# POWER_METER.net
KiCad netlist of a schematic drawn in EAGLE
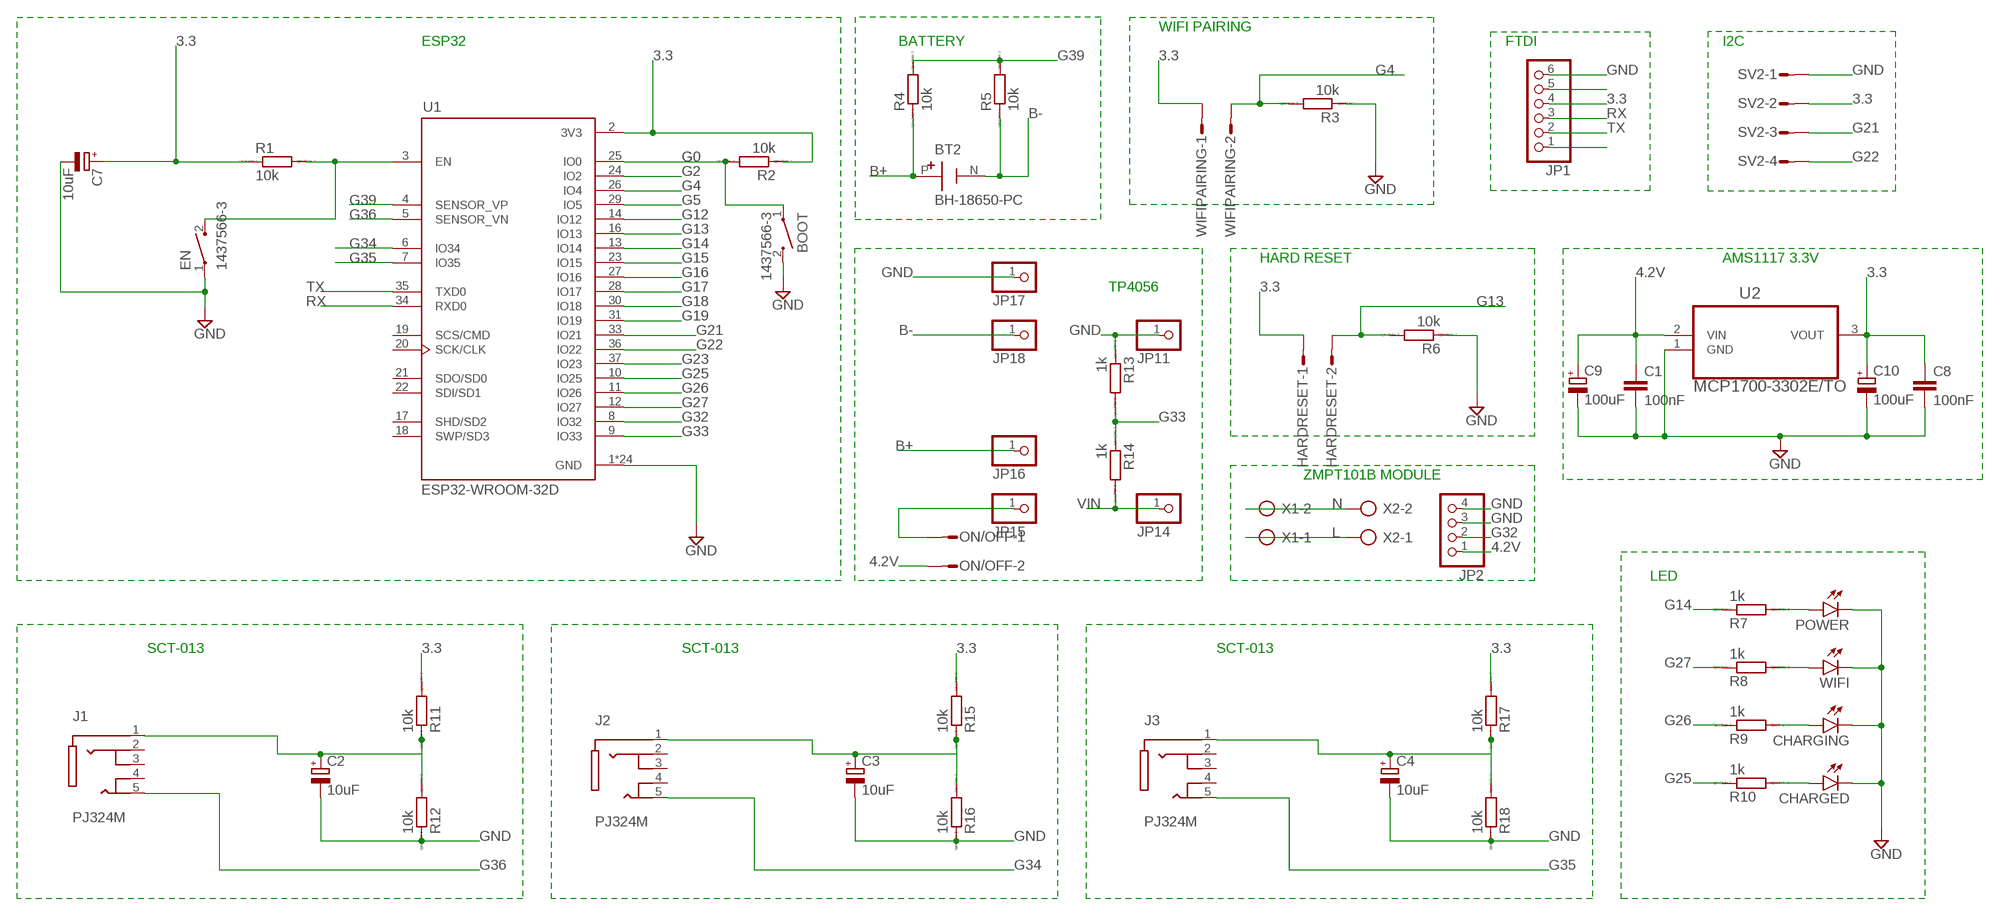
[diagram p0: schematic, sheet 1]

(export (version "E")
  (design (tool "Eeschema 10.0.6"))
  (components
    (comp (ref "BOOT")
      (value "1437566-3")
      (footprint "eagle-import:SW_1437566-3")
      (fields (field (name "MF") "TE Connectivity"))
      (libsource (lib "eagle-import") (part "1437566-3"))
    )
    (comp (ref "BT2")
      (value "BH-18650-PC")
      (footprint "eagle-import:BAT_BH-18650-PC")
      (fields (field (name "MF") "MPD (Memory"))
      (libsource (lib "eagle-import") (part "BH-18650-PC"))
    )
    (comp (ref "C1")
      (value "100nF")
      (footprint "eagle-import:C1206K")
      (libsource (lib "eagle-import") (part "C-EUC1206K"))
    )
    (comp (ref "C2")
      (value "10uF")
      (footprint "eagle-import:E2,5-6")
      (libsource (lib "eagle-import") (part "CPOL-EUE2.5-6"))
    )
    (comp (ref "C3")
      (value "10uF")
      (footprint "eagle-import:E2,5-6")
      (libsource (lib "eagle-import") (part "CPOL-EUE2.5-6"))
    )
    (comp (ref "C4")
      (value "10uF")
      (footprint "eagle-import:E2,5-6")
      (libsource (lib "eagle-import") (part "CPOL-EUE2.5-6"))
    )
    (comp (ref "C7")
      (value "10uF")
      (footprint "eagle-import:E2,5-6")
      (libsource (lib "eagle-import") (part "CPOL-EUE2.5-6"))
    )
    (comp (ref "C8")
      (value "100nF")
      (footprint "eagle-import:C1206K")
      (libsource (lib "eagle-import") (part "C-EUC1206K"))
    )
    (comp (ref "C9")
      (value "100uF")
      (footprint "eagle-import:E2,5-6")
      (libsource (lib "eagle-import") (part "CPOL-EUE2.5-6"))
    )
    (comp (ref "C10")
      (value "100uF")
      (footprint "eagle-import:E2,5-6")
      (libsource (lib "eagle-import") (part "CPOL-EUE2.5-6"))
    )
    (comp (ref "CHARGED")
      (value "LEDCHIPLED_1206")
      (footprint "eagle-import:CHIPLED_1206")
      (libsource (lib "eagle-import") (part "LEDCHIPLED_1206"))
    )
    (comp (ref "CHARGING")
      (value "LEDCHIPLED_1206")
      (footprint "eagle-import:CHIPLED_1206")
      (libsource (lib "eagle-import") (part "LEDCHIPLED_1206"))
    )
    (comp (ref "EN")
      (value "1437566-3")
      (footprint "eagle-import:SW_1437566-3")
      (fields (field (name "MF") "TE Connectivity"))
      (libsource (lib "eagle-import") (part "1437566-3"))
    )
    (comp (ref "HARDRESET")
      (value "S02P")
      (footprint "eagle-import:S02P")
      (libsource (lib "eagle-import") (part "S02P"))
    )
    (comp (ref "J1")
      (value "PJ324M")
      (footprint "eagle-import:WENZHOU_PJ324M")
      (fields (field (name "MF") "Wenzhou QingPu Electronics Co.Ltd"))
      (libsource (lib "eagle-import") (part "PJ324M"))
    )
    (comp (ref "J2")
      (value "PJ324M")
      (footprint "eagle-import:WENZHOU_PJ324M")
      (fields (field (name "MF") "Wenzhou QingPu Electronics Co.Ltd"))
      (libsource (lib "eagle-import") (part "PJ324M"))
    )
    (comp (ref "J3")
      (value "PJ324M")
      (footprint "eagle-import:WENZHOU_PJ324M")
      (fields (field (name "MF") "Wenzhou QingPu Electronics Co.Ltd"))
      (libsource (lib "eagle-import") (part "PJ324M"))
    )
    (comp (ref "JP1")
      (value "PINHD-1X6/90")
      (footprint "eagle-import:1X06_90")
      (libsource (lib "eagle-import") (part "PINHD-1X6/90"))
    )
    (comp (ref "JP2")
      (value "PINHD-1X4")
      (footprint "eagle-import:1X04")
      (libsource (lib "eagle-import") (part "PINHD-1X4"))
    )
    (comp (ref "JP11")
      (value "PINHD-1X1")
      (footprint "eagle-import:1X01")
      (libsource (lib "eagle-import") (part "PINHD-1X1"))
    )
    (comp (ref "JP14")
      (value "PINHD-1X1")
      (footprint "eagle-import:1X01")
      (libsource (lib "eagle-import") (part "PINHD-1X1"))
    )
    (comp (ref "JP15")
      (value "PINHD-1X1")
      (footprint "eagle-import:1X01")
      (libsource (lib "eagle-import") (part "PINHD-1X1"))
    )
    (comp (ref "JP16")
      (value "PINHD-1X1")
      (footprint "eagle-import:1X01")
      (libsource (lib "eagle-import") (part "PINHD-1X1"))
    )
    (comp (ref "JP17")
      (value "PINHD-1X1")
      (footprint "eagle-import:1X01")
      (libsource (lib "eagle-import") (part "PINHD-1X1"))
    )
    (comp (ref "JP18")
      (value "PINHD-1X1")
      (footprint "eagle-import:1X01")
      (libsource (lib "eagle-import") (part "PINHD-1X1"))
    )
    (comp (ref "ON/OFF")
      (value "S02P")
      (footprint "eagle-import:S02P")
      (libsource (lib "eagle-import") (part "S02P"))
    )
    (comp (ref "POWER")
      (value "LEDCHIPLED_1206")
      (footprint "eagle-import:CHIPLED_1206")
      (libsource (lib "eagle-import") (part "LEDCHIPLED_1206"))
    )
    (comp (ref "R1")
      (value "10k")
      (footprint "eagle-import:R1206")
      (libsource (lib "eagle-import") (part "RR1206"))
    )
    (comp (ref "R2")
      (value "10k")
      (footprint "eagle-import:R1206")
      (libsource (lib "eagle-import") (part "RR1206"))
    )
    (comp (ref "R3")
      (value "10k")
      (footprint "eagle-import:R1206")
      (libsource (lib "eagle-import") (part "RR1206"))
    )
    (comp (ref "R4")
      (value "10k")
      (footprint "eagle-import:R1206")
      (libsource (lib "eagle-import") (part "RR1206"))
    )
    (comp (ref "R5")
      (value "10k")
      (footprint "eagle-import:R1206")
      (libsource (lib "eagle-import") (part "RR1206"))
    )
    (comp (ref "R6")
      (value "10k")
      (footprint "eagle-import:R1206")
      (libsource (lib "eagle-import") (part "RR1206"))
    )
    (comp (ref "R7")
      (value "1k")
      (footprint "eagle-import:R1206")
      (libsource (lib "eagle-import") (part "RR1206"))
    )
    (comp (ref "R8")
      (value "1k")
      (footprint "eagle-import:R1206")
      (libsource (lib "eagle-import") (part "RR1206"))
    )
    (comp (ref "R9")
      (value "1k")
      (footprint "eagle-import:R1206")
      (libsource (lib "eagle-import") (part "RR1206"))
    )
    (comp (ref "R10")
      (value "1k")
      (footprint "eagle-import:R1206")
      (libsource (lib "eagle-import") (part "RR1206"))
    )
    (comp (ref "R11")
      (value "10k")
      (footprint "eagle-import:R1206")
      (libsource (lib "eagle-import") (part "RR1206"))
    )
    (comp (ref "R12")
      (value "10k")
      (footprint "eagle-import:R1206")
      (libsource (lib "eagle-import") (part "RR1206"))
    )
    (comp (ref "R13")
      (value "1k")
      (footprint "eagle-import:R1206")
      (libsource (lib "eagle-import") (part "RR1206"))
    )
    (comp (ref "R14")
      (value "1k")
      (footprint "eagle-import:R1206")
      (libsource (lib "eagle-import") (part "RR1206"))
    )
    (comp (ref "R15")
      (value "10k")
      (footprint "eagle-import:R1206")
      (libsource (lib "eagle-import") (part "RR1206"))
    )
    (comp (ref "R16")
      (value "10k")
      (footprint "eagle-import:R1206")
      (libsource (lib "eagle-import") (part "RR1206"))
    )
    (comp (ref "R17")
      (value "10k")
      (footprint "eagle-import:R1206")
      (libsource (lib "eagle-import") (part "RR1206"))
    )
    (comp (ref "R18")
      (value "10k")
      (footprint "eagle-import:R1206")
      (libsource (lib "eagle-import") (part "RR1206"))
    )
    (comp (ref "SV2")
      (value "S04P")
      (footprint "eagle-import:S04P")
      (libsource (lib "eagle-import") (part "S04P"))
    )
    (comp (ref "U1")
      (value "ESP32-WROOM-32D")
      (footprint "eagle-import:MODULE_ESP32-WROOM-32D")
      (fields (field (name "MF") "Espressif Systems"))
      (libsource (lib "eagle-import") (part "ESP32-WROOM-32D"))
    )
    (comp (ref "U2")
      (value "MCP1700-3302E/TO")
      (footprint "eagle-import:TO127P254X495-3")
      (fields (field (name "MF") "Microchip"))
      (libsource (lib "eagle-import") (part "MCP1700-3302E/TO"))
    )
    (comp (ref "WIFI")
      (value "LEDCHIPLED_1206")
      (footprint "eagle-import:CHIPLED_1206")
      (libsource (lib "eagle-import") (part "LEDCHIPLED_1206"))
    )
    (comp (ref "WIFIPAIRING")
      (value "S02P")
      (footprint "eagle-import:S02P")
      (libsource (lib "eagle-import") (part "S02P"))
    )
    (comp (ref "X1")
      (value "AK500/2")
      (footprint "eagle-import:AK500_2")
      (libsource (lib "eagle-import") (part "AK500/2"))
    )
    (comp (ref "X2")
      (value "AK500/2")
      (footprint "eagle-import:AK500_2")
      (libsource (lib "eagle-import") (part "AK500/2"))
    )
  )
  (nets
    (net (code "1") (name "/3.3") (class "Default")
      (node (ref "C10") (pin "+") (pinfunction "+_+") (pintype "passive"))
      (node (ref "C7") (pin "+") (pinfunction "+_+") (pintype "passive"))
      (node (ref "C8") (pin "1") (pinfunction "1_1") (pintype "passive"))
      (node (ref "HARDRESET") (pin "1") (pinfunction "S_1") (pintype "passive"))
      (node (ref "JP1") (pin "4") (pinfunction "4_4") (pintype "passive"))
      (node (ref "R1") (pin "1") (pinfunction "1_1") (pintype "passive"))
      (node (ref "R11") (pin "2") (pinfunction "2_2") (pintype "passive"))
      (node (ref "R15") (pin "2") (pinfunction "2_2") (pintype "passive"))
      (node (ref "R17") (pin "2") (pinfunction "2_2") (pintype "passive"))
      (node (ref "R2") (pin "1") (pinfunction "1_1") (pintype "passive"))
      (node (ref "SV2") (pin "2") (pinfunction "S_2") (pintype "passive"))
      (node (ref "U1") (pin "2") (pinfunction "3V3_2") (pintype "power_in"))
      (node (ref "U2") (pin "3") (pinfunction "VOUT_3") (pintype "output"))
      (node (ref "WIFIPAIRING") (pin "1") (pinfunction "S_1") (pintype "passive"))
    )
    (net (code "2") (name "/4.2V") (class "Default")
      (node (ref "C1") (pin "1") (pinfunction "1_1") (pintype "passive"))
      (node (ref "C9") (pin "+") (pinfunction "+_+") (pintype "passive"))
      (node (ref "JP2") (pin "1") (pinfunction "1_1") (pintype "passive"))
      (node (ref "ON/OFF") (pin "2") (pinfunction "S_2") (pintype "passive"))
      (node (ref "U2") (pin "2") (pinfunction "VIN_2") (pintype "input"))
    )
    (net (code "3") (name "/B+") (class "Default")
      (node (ref "BT2") (pin "P") (pinfunction "+_P") (pintype "passive"))
      (node (ref "JP16") (pin "1") (pinfunction "1_1") (pintype "passive"))
      (node (ref "R4") (pin "1") (pinfunction "1_1") (pintype "passive"))
    )
    (net (code "4") (name "/B-") (class "Default")
      (node (ref "BT2") (pin "N") (pinfunction "-_N") (pintype "passive"))
      (node (ref "JP18") (pin "1") (pinfunction "1_1") (pintype "passive"))
      (node (ref "R5") (pin "1") (pinfunction "1_1") (pintype "passive"))
    )
    (net (code "5") (name "/G0") (class "Default")
      (node (ref "BOOT") (pin "1") (pinfunction "1_1") (pintype "passive"))
      (node (ref "R2") (pin "2") (pinfunction "2_2") (pintype "passive"))
      (node (ref "U1") (pin "25") (pinfunction "IO0_25") (pintype "bidirectional"))
    )
    (net (code "6") (name "/G2") (class "Default")
      (node (ref "U1") (pin "24") (pinfunction "IO2_24") (pintype "bidirectional"))
    )
    (net (code "7") (name "/G4") (class "Default")
      (node (ref "R3") (pin "2") (pinfunction "2_2") (pintype "passive"))
      (node (ref "U1") (pin "26") (pinfunction "IO4_26") (pintype "bidirectional"))
      (node (ref "WIFIPAIRING") (pin "2") (pinfunction "S_2") (pintype "passive"))
    )
    (net (code "8") (name "/G5") (class "Default")
      (node (ref "U1") (pin "29") (pinfunction "IO5_29") (pintype "bidirectional"))
    )
    (net (code "9") (name "/G12") (class "Default")
      (node (ref "U1") (pin "14") (pinfunction "IO12_14") (pintype "bidirectional"))
    )
    (net (code "10") (name "/G13") (class "Default")
      (node (ref "HARDRESET") (pin "2") (pinfunction "S_2") (pintype "passive"))
      (node (ref "R6") (pin "2") (pinfunction "2_2") (pintype "passive"))
      (node (ref "U1") (pin "16") (pinfunction "IO13_16") (pintype "bidirectional"))
    )
    (net (code "11") (name "/G14") (class "Default")
      (node (ref "R7") (pin "1") (pinfunction "1_1") (pintype "passive"))
      (node (ref "U1") (pin "13") (pinfunction "IO14_13") (pintype "bidirectional"))
    )
    (net (code "12") (name "/G15") (class "Default")
      (node (ref "U1") (pin "23") (pinfunction "IO15_23") (pintype "bidirectional"))
    )
    (net (code "13") (name "/G16") (class "Default")
      (node (ref "U1") (pin "27") (pinfunction "IO16_27") (pintype "bidirectional"))
    )
    (net (code "14") (name "/G17") (class "Default")
      (node (ref "U1") (pin "28") (pinfunction "IO17_28") (pintype "bidirectional"))
    )
    (net (code "15") (name "/G18") (class "Default")
      (node (ref "U1") (pin "30") (pinfunction "IO18_30") (pintype "bidirectional"))
    )
    (net (code "16") (name "/G19") (class "Default")
      (node (ref "U1") (pin "31") (pinfunction "IO19_31") (pintype "bidirectional"))
    )
    (net (code "17") (name "/G21") (class "Default")
      (node (ref "SV2") (pin "3") (pinfunction "S_3") (pintype "passive"))
      (node (ref "U1") (pin "33") (pinfunction "IO21_33") (pintype "bidirectional"))
    )
    (net (code "18") (name "/G22") (class "Default")
      (node (ref "SV2") (pin "4") (pinfunction "S_4") (pintype "passive"))
      (node (ref "U1") (pin "36") (pinfunction "IO22_36") (pintype "bidirectional"))
    )
    (net (code "19") (name "/G23") (class "Default")
      (node (ref "U1") (pin "37") (pinfunction "IO23_37") (pintype "bidirectional"))
    )
    (net (code "20") (name "/G25") (class "Default")
      (node (ref "R10") (pin "1") (pinfunction "1_1") (pintype "passive"))
      (node (ref "U1") (pin "10") (pinfunction "IO25_10") (pintype "bidirectional"))
    )
    (net (code "21") (name "/G26") (class "Default")
      (node (ref "R9") (pin "1") (pinfunction "1_1") (pintype "passive"))
      (node (ref "U1") (pin "11") (pinfunction "IO26_11") (pintype "bidirectional"))
    )
    (net (code "22") (name "/G27") (class "Default")
      (node (ref "R8") (pin "1") (pinfunction "1_1") (pintype "passive"))
      (node (ref "U1") (pin "12") (pinfunction "IO27_12") (pintype "bidirectional"))
    )
    (net (code "23") (name "/G32") (class "Default")
      (node (ref "JP2") (pin "2") (pinfunction "2_2") (pintype "passive"))
      (node (ref "U1") (pin "8") (pinfunction "IO32_8") (pintype "bidirectional"))
    )
    (net (code "24") (name "/G33") (class "Default")
      (node (ref "R13") (pin "2") (pinfunction "2_2") (pintype "passive"))
      (node (ref "R14") (pin "1") (pinfunction "1_1") (pintype "passive"))
      (node (ref "U1") (pin "9") (pinfunction "IO33_9") (pintype "bidirectional"))
    )
    (net (code "25") (name "/G34") (class "Default")
      (node (ref "J2") (pin "5") (pinfunction "TIP_2_5") (pintype "passive"))
      (node (ref "U1") (pin "6") (pinfunction "IO34_6") (pintype "input"))
    )
    (net (code "26") (name "/G35") (class "Default")
      (node (ref "J3") (pin "5") (pinfunction "TIP_2_5") (pintype "passive"))
      (node (ref "U1") (pin "7") (pinfunction "IO35_7") (pintype "input"))
    )
    (net (code "27") (name "/G36") (class "Default")
      (node (ref "J1") (pin "5") (pinfunction "TIP_2_5") (pintype "passive"))
      (node (ref "U1") (pin "5") (pinfunction "SENSOR_VN_5") (pintype "input"))
    )
    (net (code "28") (name "/G39") (class "Default")
      (node (ref "R4") (pin "2") (pinfunction "2_2") (pintype "passive"))
      (node (ref "R5") (pin "2") (pinfunction "2_2") (pintype "passive"))
      (node (ref "U1") (pin "4") (pinfunction "SENSOR_VP_4") (pintype "input"))
    )
    (net (code "29") (name "/L") (class "Default")
      (node (ref "X1") (pin "1") (pinfunction "KL_1") (pintype "passive"))
      (node (ref "X2") (pin "1") (pinfunction "KL_1") (pintype "passive"))
    )
    (net (code "30") (name "/N") (class "Default")
      (node (ref "X1") (pin "2") (pinfunction "KL_2") (pintype "passive"))
      (node (ref "X2") (pin "2") (pinfunction "KL_2") (pintype "passive"))
    )
    (net (code "31") (name "/RX") (class "Default")
      (node (ref "JP1") (pin "3") (pinfunction "3_3") (pintype "passive"))
      (node (ref "U1") (pin "34") (pinfunction "RXD0_34") (pintype "bidirectional"))
    )
    (net (code "32") (name "/TX") (class "Default")
      (node (ref "JP1") (pin "2") (pinfunction "2_2") (pintype "passive"))
      (node (ref "U1") (pin "35") (pinfunction "TXD0_35") (pintype "bidirectional"))
    )
    (net (code "33") (name "/VIN") (class "Default")
      (node (ref "JP14") (pin "1") (pinfunction "1_1") (pintype "passive"))
      (node (ref "R14") (pin "2") (pinfunction "2_2") (pintype "passive"))
    )
    (net (code "34") (name "GND") (class "Default")
      (node (ref "BOOT") (pin "2") (pinfunction "2_2") (pintype "passive"))
      (node (ref "C1") (pin "2") (pinfunction "2_2") (pintype "passive"))
      (node (ref "C10") (pin "-") (pinfunction "-_-") (pintype "passive"))
      (node (ref "C2") (pin "-") (pinfunction "-_-") (pintype "passive"))
      (node (ref "C3") (pin "-") (pinfunction "-_-") (pintype "passive"))
      (node (ref "C4") (pin "-") (pinfunction "-_-") (pintype "passive"))
      (node (ref "C7") (pin "-") (pinfunction "-_-") (pintype "passive"))
      (node (ref "C8") (pin "2") (pinfunction "2_2") (pintype "passive"))
      (node (ref "C9") (pin "-") (pinfunction "-_-") (pintype "passive"))
      (node (ref "CHARGED") (pin "C") (pinfunction "C_C") (pintype "passive"))
      (node (ref "CHARGING") (pin "C") (pinfunction "C_C") (pintype "passive"))
      (node (ref "EN") (pin "1") (pinfunction "1_1") (pintype "passive"))
      (node (ref "JP1") (pin "6") (pinfunction "6_6") (pintype "passive"))
      (node (ref "JP11") (pin "1") (pinfunction "1_1") (pintype "passive"))
      (node (ref "JP17") (pin "1") (pinfunction "1_1") (pintype "passive"))
      (node (ref "JP2") (pin "3") (pinfunction "3_3") (pintype "passive"))
      (node (ref "JP2") (pin "4") (pinfunction "4_4") (pintype "passive"))
      (node (ref "POWER") (pin "C") (pinfunction "C_C") (pintype "passive"))
      (node (ref "R12") (pin "1") (pinfunction "1_1") (pintype "passive"))
      (node (ref "R13") (pin "1") (pinfunction "1_1") (pintype "passive"))
      (node (ref "R16") (pin "1") (pinfunction "1_1") (pintype "passive"))
      (node (ref "R18") (pin "1") (pinfunction "1_1") (pintype "passive"))
      (node (ref "R3") (pin "1") (pinfunction "1_1") (pintype "passive"))
      (node (ref "R6") (pin "1") (pinfunction "1_1") (pintype "passive"))
      (node (ref "SV2") (pin "1") (pinfunction "S_1") (pintype "passive"))
      (node (ref "U1") (pin "1") (pinfunction "GND_1") (pintype "power_in"))
      (node (ref "U1") (pin "15") (pinfunction "GND_15") (pintype "power_in"))
      (node (ref "U1") (pin "38") (pinfunction "GND_38") (pintype "power_in"))
      (node (ref "U1") (pin "39_1") (pinfunction "GND_39_1") (pintype "power_in"))
      (node (ref "U1") (pin "39_10") (pinfunction "GND_39_10") (pintype "power_in"))
      (node (ref "U1") (pin "39_11") (pinfunction "GND_39_11") (pintype "power_in"))
      (node (ref "U1") (pin "39_12") (pinfunction "GND_39_12") (pintype "power_in"))
      (node (ref "U1") (pin "39_13") (pinfunction "GND_39_13") (pintype "power_in"))
      (node (ref "U1") (pin "39_14") (pinfunction "GND_39_14") (pintype "power_in"))
      (node (ref "U1") (pin "39_15") (pinfunction "GND_39_15") (pintype "power_in"))
      (node (ref "U1") (pin "39_16") (pinfunction "GND_39_16") (pintype "power_in"))
      (node (ref "U1") (pin "39_17") (pinfunction "GND_39_17") (pintype "power_in"))
      (node (ref "U1") (pin "39_18") (pinfunction "GND_39_18") (pintype "power_in"))
      (node (ref "U1") (pin "39_19") (pinfunction "GND_39_19") (pintype "power_in"))
      (node (ref "U1") (pin "39_2") (pinfunction "GND_39_2") (pintype "power_in"))
      (node (ref "U1") (pin "39_20") (pinfunction "GND_39_20") (pintype "power_in"))
      (node (ref "U1") (pin "39_21") (pinfunction "GND_39_21") (pintype "power_in"))
      (node (ref "U1") (pin "39_3") (pinfunction "GND_39_3") (pintype "power_in"))
      (node (ref "U1") (pin "39_4") (pinfunction "GND_39_4") (pintype "power_in"))
      (node (ref "U1") (pin "39_5") (pinfunction "GND_39_5") (pintype "power_in"))
      (node (ref "U1") (pin "39_6") (pinfunction "GND_39_6") (pintype "power_in"))
      (node (ref "U1") (pin "39_7") (pinfunction "GND_39_7") (pintype "power_in"))
      (node (ref "U1") (pin "39_8") (pinfunction "GND_39_8") (pintype "power_in"))
      (node (ref "U1") (pin "39_9") (pinfunction "GND_39_9") (pintype "power_in"))
      (node (ref "U2") (pin "1") (pinfunction "GND_1") (pintype "passive"))
      (node (ref "WIFI") (pin "C") (pinfunction "C_C") (pintype "passive"))
    )
    (net (code "35") (name "Net-(CHARGED-PadA)") (class "Default")
      (node (ref "CHARGED") (pin "A") (pinfunction "A_A") (pintype "passive"))
      (node (ref "R10") (pin "2") (pinfunction "2_2") (pintype "passive"))
    )
    (net (code "36") (name "Net-(CHARGING-PadA)") (class "Default")
      (node (ref "CHARGING") (pin "A") (pinfunction "A_A") (pintype "passive"))
      (node (ref "R9") (pin "2") (pinfunction "2_2") (pintype "passive"))
    )
    (net (code "37") (name "Net-(J1-SLEEVE)") (class "Default")
      (node (ref "C2") (pin "+") (pinfunction "+_+") (pintype "passive"))
      (node (ref "J1") (pin "1") (pinfunction "SLEEVE_1") (pintype "passive"))
      (node (ref "R11") (pin "1") (pinfunction "1_1") (pintype "passive"))
      (node (ref "R12") (pin "2") (pinfunction "2_2") (pintype "passive"))
    )
    (net (code "38") (name "Net-(J2-SLEEVE)") (class "Default")
      (node (ref "C3") (pin "+") (pinfunction "+_+") (pintype "passive"))
      (node (ref "J2") (pin "1") (pinfunction "SLEEVE_1") (pintype "passive"))
      (node (ref "R15") (pin "1") (pinfunction "1_1") (pintype "passive"))
      (node (ref "R16") (pin "2") (pinfunction "2_2") (pintype "passive"))
    )
    (net (code "39") (name "Net-(J3-SLEEVE)") (class "Default")
      (node (ref "C4") (pin "+") (pinfunction "+_+") (pintype "passive"))
      (node (ref "J3") (pin "1") (pinfunction "SLEEVE_1") (pintype "passive"))
      (node (ref "R17") (pin "1") (pinfunction "1_1") (pintype "passive"))
      (node (ref "R18") (pin "2") (pinfunction "2_2") (pintype "passive"))
    )
    (net (code "40") (name "Net-(ON/OFFA-S)") (class "Default")
      (node (ref "JP15") (pin "1") (pinfunction "1_1") (pintype "passive"))
      (node (ref "ON/OFF") (pin "1") (pinfunction "S_1") (pintype "passive"))
    )
    (net (code "41") (name "Net-(POWER-PadA)") (class "Default")
      (node (ref "POWER") (pin "A") (pinfunction "A_A") (pintype "passive"))
      (node (ref "R7") (pin "2") (pinfunction "2_2") (pintype "passive"))
    )
    (net (code "42") (name "Net-(R8-Pad2)") (class "Default")
      (node (ref "R8") (pin "2") (pinfunction "2_2") (pintype "passive"))
      (node (ref "WIFI") (pin "A") (pinfunction "A_A") (pintype "passive"))
    )
    (net (code "43") (name "Net-(U1-EN)") (class "Default")
      (node (ref "EN") (pin "2") (pinfunction "2_2") (pintype "passive"))
      (node (ref "R1") (pin "2") (pinfunction "2_2") (pintype "passive"))
      (node (ref "U1") (pin "3") (pinfunction "EN_3") (pintype "input"))
    )
    (net (code "44") (name "unconnected-(J1-RING_1-Pad2)") (class "Default")
      (node (ref "J1") (pin "2") (pinfunction "RING_1_2") (pintype "passive"))
    )
    (net (code "45") (name "unconnected-(J1-RING_2-Pad3)") (class "Default")
      (node (ref "J1") (pin "3") (pinfunction "RING_2_3") (pintype "passive"))
    )
    (net (code "46") (name "unconnected-(J1-TIP_1-Pad4)") (class "Default")
      (node (ref "J1") (pin "4") (pinfunction "TIP_1_4") (pintype "passive"))
    )
    (net (code "47") (name "unconnected-(J2-RING_1-Pad2)") (class "Default")
      (node (ref "J2") (pin "2") (pinfunction "RING_1_2") (pintype "passive"))
    )
    (net (code "48") (name "unconnected-(J2-RING_2-Pad3)") (class "Default")
      (node (ref "J2") (pin "3") (pinfunction "RING_2_3") (pintype "passive"))
    )
    (net (code "49") (name "unconnected-(J2-TIP_1-Pad4)") (class "Default")
      (node (ref "J2") (pin "4") (pinfunction "TIP_1_4") (pintype "passive"))
    )
    (net (code "50") (name "unconnected-(J3-RING_1-Pad2)") (class "Default")
      (node (ref "J3") (pin "2") (pinfunction "RING_1_2") (pintype "passive"))
    )
    (net (code "51") (name "unconnected-(J3-RING_2-Pad3)") (class "Default")
      (node (ref "J3") (pin "3") (pinfunction "RING_2_3") (pintype "passive"))
    )
    (net (code "52") (name "unconnected-(J3-TIP_1-Pad4)") (class "Default")
      (node (ref "J3") (pin "4") (pinfunction "TIP_1_4") (pintype "passive"))
    )
    (net (code "53") (name "unconnected-(JP1-Pad1)") (class "Default")
      (node (ref "JP1") (pin "1") (pinfunction "1_1") (pintype "passive"))
    )
    (net (code "54") (name "unconnected-(JP1-Pad5)") (class "Default")
      (node (ref "JP1") (pin "5") (pinfunction "5_5") (pintype "passive"))
    )
    (net (code "55") (name "unconnected-(U1-SCK{slash}CLK-Pad20)") (class "Default")
      (node (ref "U1") (pin "20") (pinfunction "SCK/CLK_20") (pintype "bidirectional"))
    )
    (net (code "56") (name "unconnected-(U1-SCS{slash}CMD-Pad19)") (class "Default")
      (node (ref "U1") (pin "19") (pinfunction "SCS/CMD_19") (pintype "bidirectional"))
    )
    (net (code "57") (name "unconnected-(U1-SDI{slash}SD1-Pad22)") (class "Default")
      (node (ref "U1") (pin "22") (pinfunction "SDI/SD1_22") (pintype "bidirectional"))
    )
    (net (code "58") (name "unconnected-(U1-SDO{slash}SD0-Pad21)") (class "Default")
      (node (ref "U1") (pin "21") (pinfunction "SDO/SD0_21") (pintype "bidirectional"))
    )
    (net (code "59") (name "unconnected-(U1-SHD{slash}SD2-Pad17)") (class "Default")
      (node (ref "U1") (pin "17") (pinfunction "SHD/SD2_17") (pintype "bidirectional"))
    )
    (net (code "60") (name "unconnected-(U1-SWP{slash}SD3-Pad18)") (class "Default")
      (node (ref "U1") (pin "18") (pinfunction "SWP/SD3_18") (pintype "bidirectional"))
    )
  )
)
